# Qwiic_Scale_test.net
KiCad netlist of a schematic drawn in EAGLE
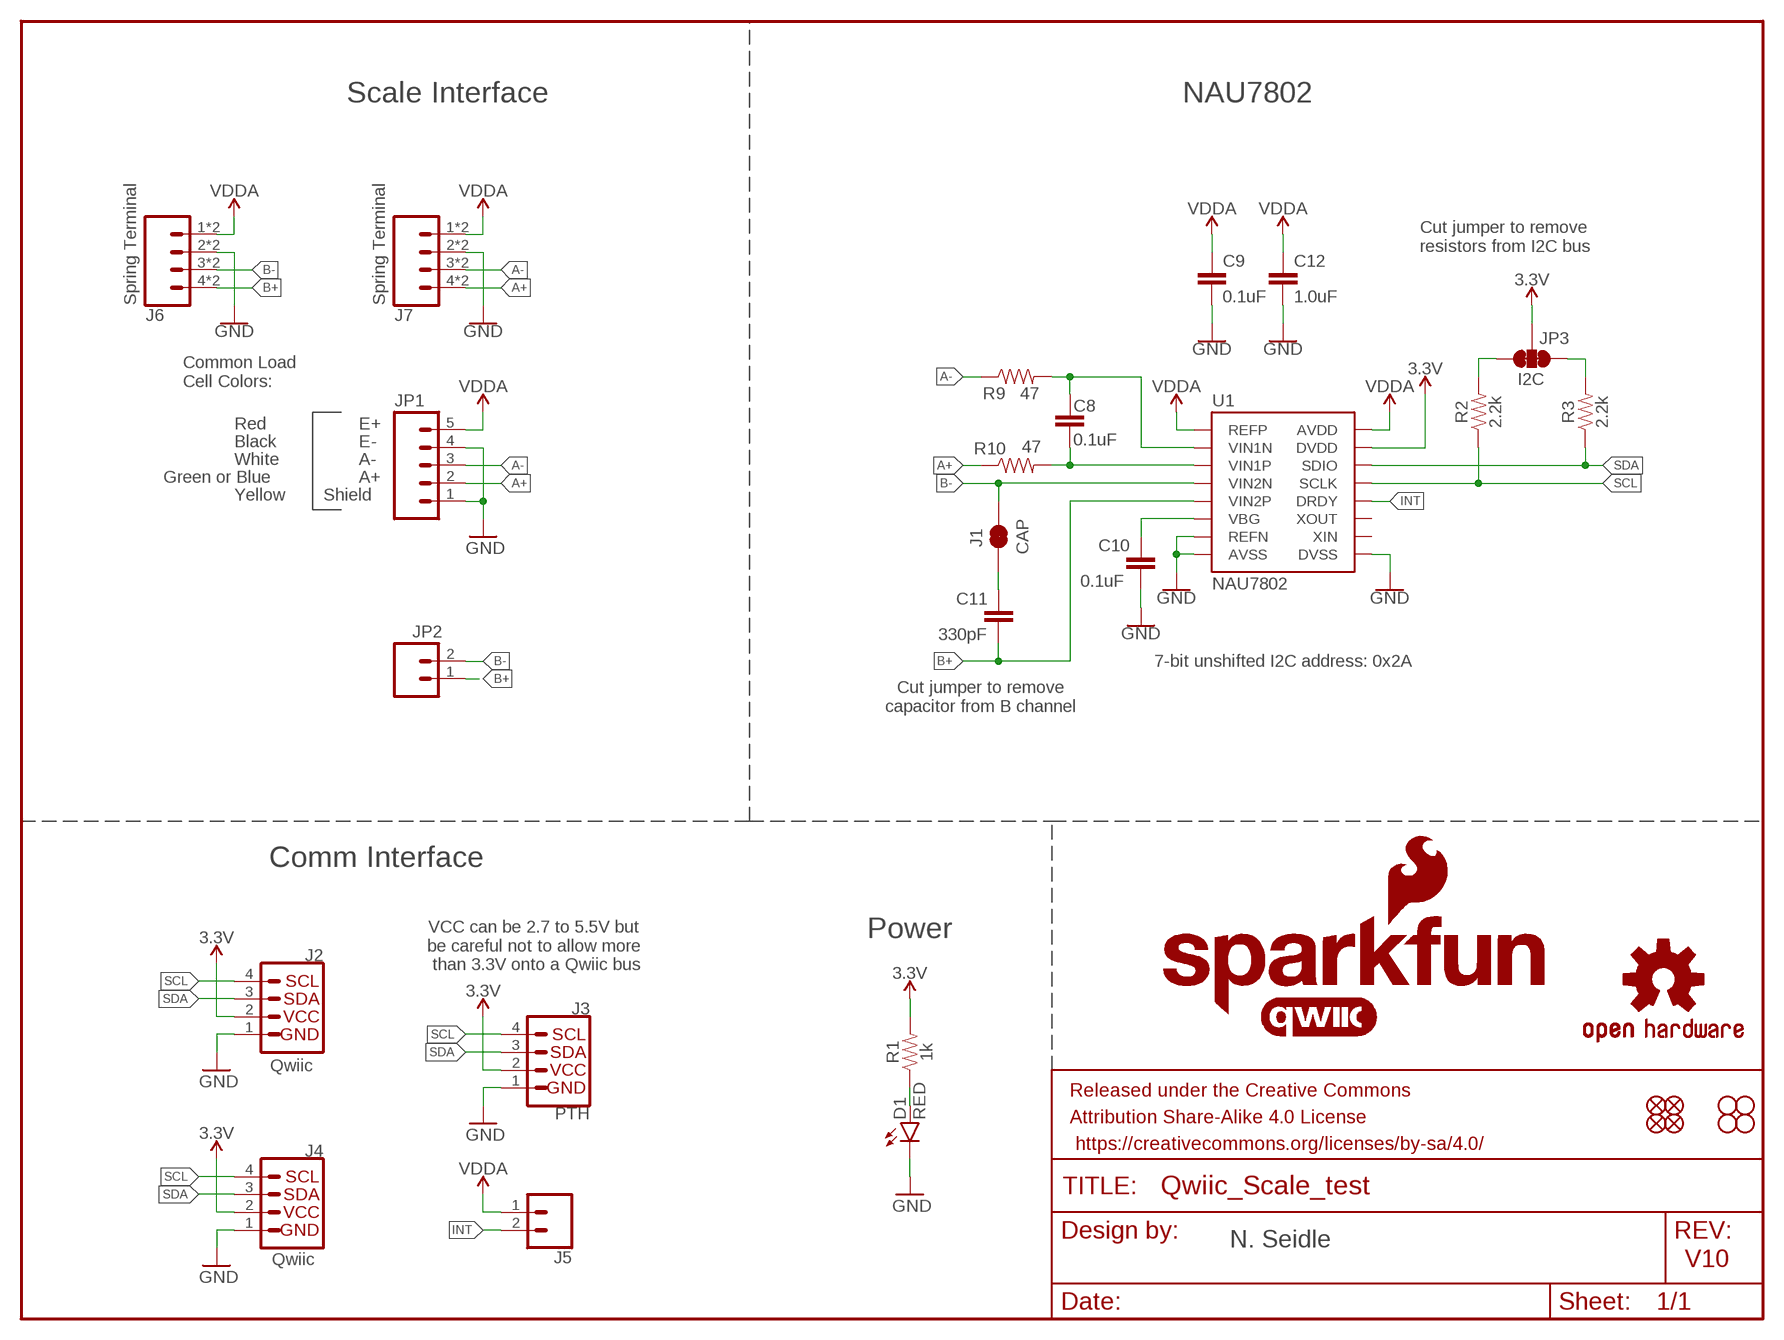
[diagram p0: schematic, sheet 1]

(export (version "E")
  (design (tool "Eeschema 10.0.6"))
  (components
    (comp (ref "C8")
      (value "0.1uF")
      (footprint "eagle-import:0603")
      (libsource (lib "eagle-import") (part "0.1UF-0603-25V-(+80/-20%)"))
    )
    (comp (ref "C9")
      (value "0.1uF")
      (footprint "eagle-import:0603")
      (libsource (lib "eagle-import") (part "0.1UF-0603-25V-(+80/-20%)"))
    )
    (comp (ref "C10")
      (value "0.1uF")
      (footprint "eagle-import:0603")
      (libsource (lib "eagle-import") (part "0.1UF-0603-25V-(+80/-20%)"))
    )
    (comp (ref "C11")
      (value "330pF")
      (footprint "eagle-import:0603")
      (libsource (lib "eagle-import") (part "330PF-0603-50V-5%"))
    )
    (comp (ref "C12")
      (value "1.0uF")
      (footprint "eagle-import:0603")
      (libsource (lib "eagle-import") (part "1.0UF-0603-16V-10%"))
    )
    (comp (ref "D1")
      (value "RED")
      (footprint "eagle-import:LED-0603")
      (libsource (lib "eagle-import") (part "LED-RED0603"))
    )
    (comp (ref "FRAME1")
      (value "FRAME-LETTER")
      (footprint "eagle-import:CREATIVE_COMMONS")
      (libsource (lib "eagle-import") (part "FRAME-LETTER"))
    )
    (comp (ref "J1")
      (value "CAP")
      (footprint "eagle-import:SMT-JUMPER_2_NC_TRACE_SILK")
      (libsource (lib "eagle-import") (part "JUMPER-SMT_2_NC_TRACE_SILK"))
    )
    (comp (ref "J2")
      (value "Qwiic")
      (footprint "eagle-import:JST04_1MM_RA")
      (libsource (lib "eagle-import") (part "I2C_STANDARDQWIIC"))
    )
    (comp (ref "J3")
      (value "PTH")
      (footprint "eagle-import:1X04_NO_SILK")
      (libsource (lib "eagle-import") (part "I2C_STANDARD_NO_SILK"))
    )
    (comp (ref "J4")
      (value "Qwiic")
      (footprint "eagle-import:JST04_1MM_RA")
      (libsource (lib "eagle-import") (part "I2C_STANDARDQWIIC"))
    )
    (comp (ref "J5")
      (value "CONN_021X02_NO_SILK")
      (footprint "eagle-import:1X02_NO_SILK")
      (libsource (lib "eagle-import") (part "CONN_021X02_NO_SILK"))
    )
    (comp (ref "J6")
      (value "Spring Terminal")
      (footprint "eagle-import:1X04_SPRING_TERMINAL")
      (libsource (lib "eagle-import") (part "CONN_04SPRING"))
    )
    (comp (ref "J7")
      (value "Spring Terminal")
      (footprint "eagle-import:1X04_SPRING_TERMINAL")
      (libsource (lib "eagle-import") (part "CONN_04SPRING"))
    )
    (comp (ref "JP1")
      (value "CONN_05NO_SILK")
      (footprint "eagle-import:1X05_NO_SILK")
      (libsource (lib "eagle-import") (part "CONN_05NO_SILK"))
    )
    (comp (ref "JP2")
      (value "CONN_021X02_NO_SILK")
      (footprint "eagle-import:1X02_NO_SILK")
      (libsource (lib "eagle-import") (part "CONN_021X02_NO_SILK"))
    )
    (comp (ref "JP3")
      (value "I2C")
      (footprint "eagle-import:SMT-JUMPER_3_2-NC_TRACE_SILK")
      (libsource (lib "eagle-import") (part "JUMPER-SMT_3_2-NC_TRACE_SILK"))
    )
    (comp (ref "JP21")
      (value "FIDUCIALUFIDUCIAL")
      (footprint "eagle-import:MICRO-FIDUCIAL")
      (libsource (lib "eagle-import") (part "FIDUCIALUFIDUCIAL"))
    )
    (comp (ref "JP31")
      (value "STAND-OFF")
      (footprint "eagle-import:STAND-OFF")
      (libsource (lib "eagle-import") (part "STAND-OFF"))
    )
    (comp (ref "JP41")
      (value "STAND-OFF")
      (footprint "eagle-import:STAND-OFF")
      (libsource (lib "eagle-import") (part "STAND-OFF"))
    )
    (comp (ref "JP61")
      (value "FIDUCIALUFIDUCIAL")
      (footprint "eagle-import:MICRO-FIDUCIAL")
      (libsource (lib "eagle-import") (part "FIDUCIALUFIDUCIAL"))
    )
    (comp (ref "JP71")
      (value "FIDUCIALUFIDUCIAL")
      (footprint "eagle-import:MICRO-FIDUCIAL")
      (libsource (lib "eagle-import") (part "FIDUCIALUFIDUCIAL"))
    )
    (comp (ref "JP81")
      (value "FIDUCIALUFIDUCIAL")
      (footprint "eagle-import:MICRO-FIDUCIAL")
      (libsource (lib "eagle-import") (part "FIDUCIALUFIDUCIAL"))
    )
    (comp (ref "JP91")
      (value "STAND-OFF")
      (footprint "eagle-import:STAND-OFF")
      (libsource (lib "eagle-import") (part "STAND-OFF"))
    )
    (comp (ref "JP101")
      (value "STAND-OFF")
      (footprint "eagle-import:STAND-OFF")
      (libsource (lib "eagle-import") (part "STAND-OFF"))
    )
    (comp (ref "LOGO1")
      (value "OSHW-LOGOMINI")
      (footprint "eagle-import:OSHW-LOGO-MINI")
      (libsource (lib "eagle-import") (part "OSHW-LOGOMINI"))
    )
    (comp (ref "LOGO2")
      (value "SFE_LOGO_NAME_FLAME.1_INCH")
      (footprint "eagle-import:SFE_LOGO_NAME_FLAME_.1")
      (libsource (lib "eagle-import") (part "SFE_LOGO_NAME_FLAME.1_INCH"))
    )
    (comp (ref "R1")
      (value "1k")
      (footprint "eagle-import:0603")
      (libsource (lib "eagle-import") (part "1KOHM-0603-1/10W-1%"))
    )
    (comp (ref "R2")
      (value "2.2k")
      (footprint "eagle-import:0603")
      (libsource (lib "eagle-import") (part "2.2KOHM-0603-1/10W-1%"))
    )
    (comp (ref "R3")
      (value "2.2k")
      (footprint "eagle-import:0603")
      (libsource (lib "eagle-import") (part "2.2KOHM-0603-1/10W-1%"))
    )
    (comp (ref "R9")
      (value "47")
      (footprint "eagle-import:0603")
      (libsource (lib "eagle-import") (part "47OHM-0603-1/10W-1%"))
    )
    (comp (ref "R10")
      (value "47")
      (footprint "eagle-import:0603")
      (libsource (lib "eagle-import") (part "47OHM-0603-1/10W-1%"))
    )
    (comp (ref "U$16")
      (value "QWIIC_LOGO_7MM")
      (footprint "eagle-import:QWIIC_7MM")
      (libsource (lib "eagle-import") (part "QWIIC_LOGO_7MM"))
    )
    (comp (ref "U1")
      (value "NAU7802")
      (footprint "eagle-import:SO16")
      (libsource (lib "eagle-import") (part "NAU7802SOIC"))
    )
  )
  (nets
    (net (code "1") (name "3.3V") (class "Default")
      (node (ref "J2") (pin "2") (pinfunction "2_2") (pintype "power_in"))
      (node (ref "J3") (pin "2") (pinfunction "2_2") (pintype "power_in"))
      (node (ref "J4") (pin "2") (pinfunction "2_2") (pintype "power_in"))
      (node (ref "JP3") (pin "2") (pinfunction "2_2") (pintype "passive"))
      (node (ref "R1") (pin "2") (pinfunction "2_2") (pintype "passive"))
      (node (ref "U1") (pin "15") (pinfunction "DVDD_15") (pintype "bidirectional"))
    )
    (net (code "2") (name "A+") (class "Default")
      (node (ref "J7") (pin "4") (pinfunction "4_4") (pintype "passive"))
      (node (ref "J7") (pin "8") (pinfunction "4_8") (pintype "passive"))
      (node (ref "JP1") (pin "2") (pinfunction "2_2") (pintype "passive"))
      (node (ref "R10") (pin "1") (pinfunction "1_1") (pintype "passive"))
    )
    (net (code "3") (name "A-") (class "Default")
      (node (ref "J7") (pin "3") (pinfunction "3_3") (pintype "passive"))
      (node (ref "J7") (pin "7") (pinfunction "3_7") (pintype "passive"))
      (node (ref "JP1") (pin "3") (pinfunction "3_3") (pintype "passive"))
      (node (ref "R9") (pin "1") (pinfunction "1_1") (pintype "passive"))
    )
    (net (code "4") (name "B+") (class "Default")
      (node (ref "C11") (pin "2") (pinfunction "2_2") (pintype "passive"))
      (node (ref "J6") (pin "4") (pinfunction "4_4") (pintype "passive"))
      (node (ref "J6") (pin "8") (pinfunction "4_8") (pintype "passive"))
      (node (ref "JP2") (pin "1") (pinfunction "1_1") (pintype "passive"))
      (node (ref "U1") (pin "5") (pinfunction "VIN2P_5") (pintype "bidirectional"))
    )
    (net (code "5") (name "B-") (class "Default")
      (node (ref "J1") (pin "2") (pinfunction "2_2") (pintype "passive"))
      (node (ref "J6") (pin "3") (pinfunction "3_3") (pintype "passive"))
      (node (ref "J6") (pin "7") (pinfunction "3_7") (pintype "passive"))
      (node (ref "JP2") (pin "2") (pinfunction "2_2") (pintype "passive"))
      (node (ref "U1") (pin "4") (pinfunction "VIN2N_4") (pintype "bidirectional"))
    )
    (net (code "6") (name "GND") (class "Default")
      (node (ref "C10") (pin "2") (pinfunction "2_2") (pintype "passive"))
      (node (ref "C12") (pin "2") (pinfunction "2_2") (pintype "passive"))
      (node (ref "C9") (pin "2") (pinfunction "2_2") (pintype "passive"))
      (node (ref "D1") (pin "C") (pinfunction "C_C") (pintype "passive"))
      (node (ref "J2") (pin "1") (pinfunction "1_1") (pintype "power_in"))
      (node (ref "J3") (pin "1") (pinfunction "1_1") (pintype "power_in"))
      (node (ref "J4") (pin "1") (pinfunction "1_1") (pintype "power_in"))
      (node (ref "J6") (pin "2") (pinfunction "2_2") (pintype "passive"))
      (node (ref "J6") (pin "6") (pinfunction "2_6") (pintype "passive"))
      (node (ref "J7") (pin "2") (pinfunction "2_2") (pintype "passive"))
      (node (ref "J7") (pin "6") (pinfunction "2_6") (pintype "passive"))
      (node (ref "JP1") (pin "1") (pinfunction "1_1") (pintype "passive"))
      (node (ref "JP1") (pin "4") (pinfunction "4_4") (pintype "passive"))
      (node (ref "U1") (pin "7") (pinfunction "REFN_7") (pintype "bidirectional"))
      (node (ref "U1") (pin "8") (pinfunction "AVSS_8") (pintype "bidirectional"))
      (node (ref "U1") (pin "9") (pinfunction "DVSS_9") (pintype "bidirectional"))
    )
    (net (code "7") (name "INT") (class "Default")
      (node (ref "J5") (pin "2") (pinfunction "2_2") (pintype "passive"))
      (node (ref "U1") (pin "12") (pinfunction "DRDY_12") (pintype "bidirectional"))
    )
    (net (code "8") (name "Net-(C11-Pad1)") (class "Default")
      (node (ref "C11") (pin "1") (pinfunction "1_1") (pintype "passive"))
      (node (ref "J1") (pin "1") (pinfunction "1_1") (pintype "passive"))
    )
    (net (code "9") (name "Net-(D1-PadA)") (class "Default")
      (node (ref "D1") (pin "A") (pinfunction "A_A") (pintype "passive"))
      (node (ref "R1") (pin "1") (pinfunction "1_1") (pintype "passive"))
    )
    (net (code "10") (name "Net-(JP3-Pad1)") (class "Default")
      (node (ref "JP3") (pin "1") (pinfunction "1_1") (pintype "passive"))
      (node (ref "R3") (pin "2") (pinfunction "2_2") (pintype "passive"))
    )
    (net (code "11") (name "Net-(JP3-Pad3)") (class "Default")
      (node (ref "JP3") (pin "3") (pinfunction "3_3") (pintype "passive"))
      (node (ref "R2") (pin "2") (pinfunction "2_2") (pintype "passive"))
    )
    (net (code "12") (name "Net-(U1-VBG)") (class "Default")
      (node (ref "C10") (pin "1") (pinfunction "1_1") (pintype "passive"))
      (node (ref "U1") (pin "6") (pinfunction "VBG_6") (pintype "bidirectional"))
    )
    (net (code "13") (name "Net-(U1-VIN1N)") (class "Default")
      (node (ref "C8") (pin "1") (pinfunction "1_1") (pintype "passive"))
      (node (ref "R9") (pin "2") (pinfunction "2_2") (pintype "passive"))
      (node (ref "U1") (pin "2") (pinfunction "VIN1N_2") (pintype "bidirectional"))
    )
    (net (code "14") (name "Net-(U1-VIN1P)") (class "Default")
      (node (ref "C8") (pin "2") (pinfunction "2_2") (pintype "passive"))
      (node (ref "R10") (pin "2") (pinfunction "2_2") (pintype "passive"))
      (node (ref "U1") (pin "3") (pinfunction "VIN1P_3") (pintype "bidirectional"))
    )
    (net (code "15") (name "SCL") (class "Default")
      (node (ref "J2") (pin "4") (pinfunction "4_4") (pintype "passive"))
      (node (ref "J3") (pin "4") (pinfunction "4_4") (pintype "passive"))
      (node (ref "J4") (pin "4") (pinfunction "4_4") (pintype "passive"))
      (node (ref "R2") (pin "1") (pinfunction "1_1") (pintype "passive"))
      (node (ref "U1") (pin "13") (pinfunction "SCLK_13") (pintype "bidirectional"))
    )
    (net (code "16") (name "SDA") (class "Default")
      (node (ref "J2") (pin "3") (pinfunction "3_3") (pintype "passive"))
      (node (ref "J3") (pin "3") (pinfunction "3_3") (pintype "passive"))
      (node (ref "J4") (pin "3") (pinfunction "3_3") (pintype "passive"))
      (node (ref "R3") (pin "1") (pinfunction "1_1") (pintype "passive"))
      (node (ref "U1") (pin "14") (pinfunction "SDIO_14") (pintype "bidirectional"))
    )
    (net (code "17") (name "VDDA") (class "Default")
      (node (ref "C12") (pin "1") (pinfunction "1_1") (pintype "passive"))
      (node (ref "C9") (pin "1") (pinfunction "1_1") (pintype "passive"))
      (node (ref "J5") (pin "1") (pinfunction "1_1") (pintype "passive"))
      (node (ref "J6") (pin "1") (pinfunction "1_1") (pintype "passive"))
      (node (ref "J6") (pin "5") (pinfunction "1_5") (pintype "passive"))
      (node (ref "J7") (pin "1") (pinfunction "1_1") (pintype "passive"))
      (node (ref "J7") (pin "5") (pinfunction "1_5") (pintype "passive"))
      (node (ref "JP1") (pin "5") (pinfunction "5_5") (pintype "passive"))
      (node (ref "U1") (pin "1") (pinfunction "REFP_1") (pintype "bidirectional"))
      (node (ref "U1") (pin "16") (pinfunction "AVDD_16") (pintype "bidirectional"))
    )
    (net (code "18") (name "unconnected-(U1-XIN-Pad10)") (class "Default")
      (node (ref "U1") (pin "10") (pinfunction "XIN_10") (pintype "bidirectional"))
    )
    (net (code "19") (name "unconnected-(U1-XOUT-Pad11)") (class "Default")
      (node (ref "U1") (pin "11") (pinfunction "XOUT_11") (pintype "bidirectional"))
    )
  )
)
